# date-shift-r1.net
KiCad netlist of a schematic drawn in EAGLE
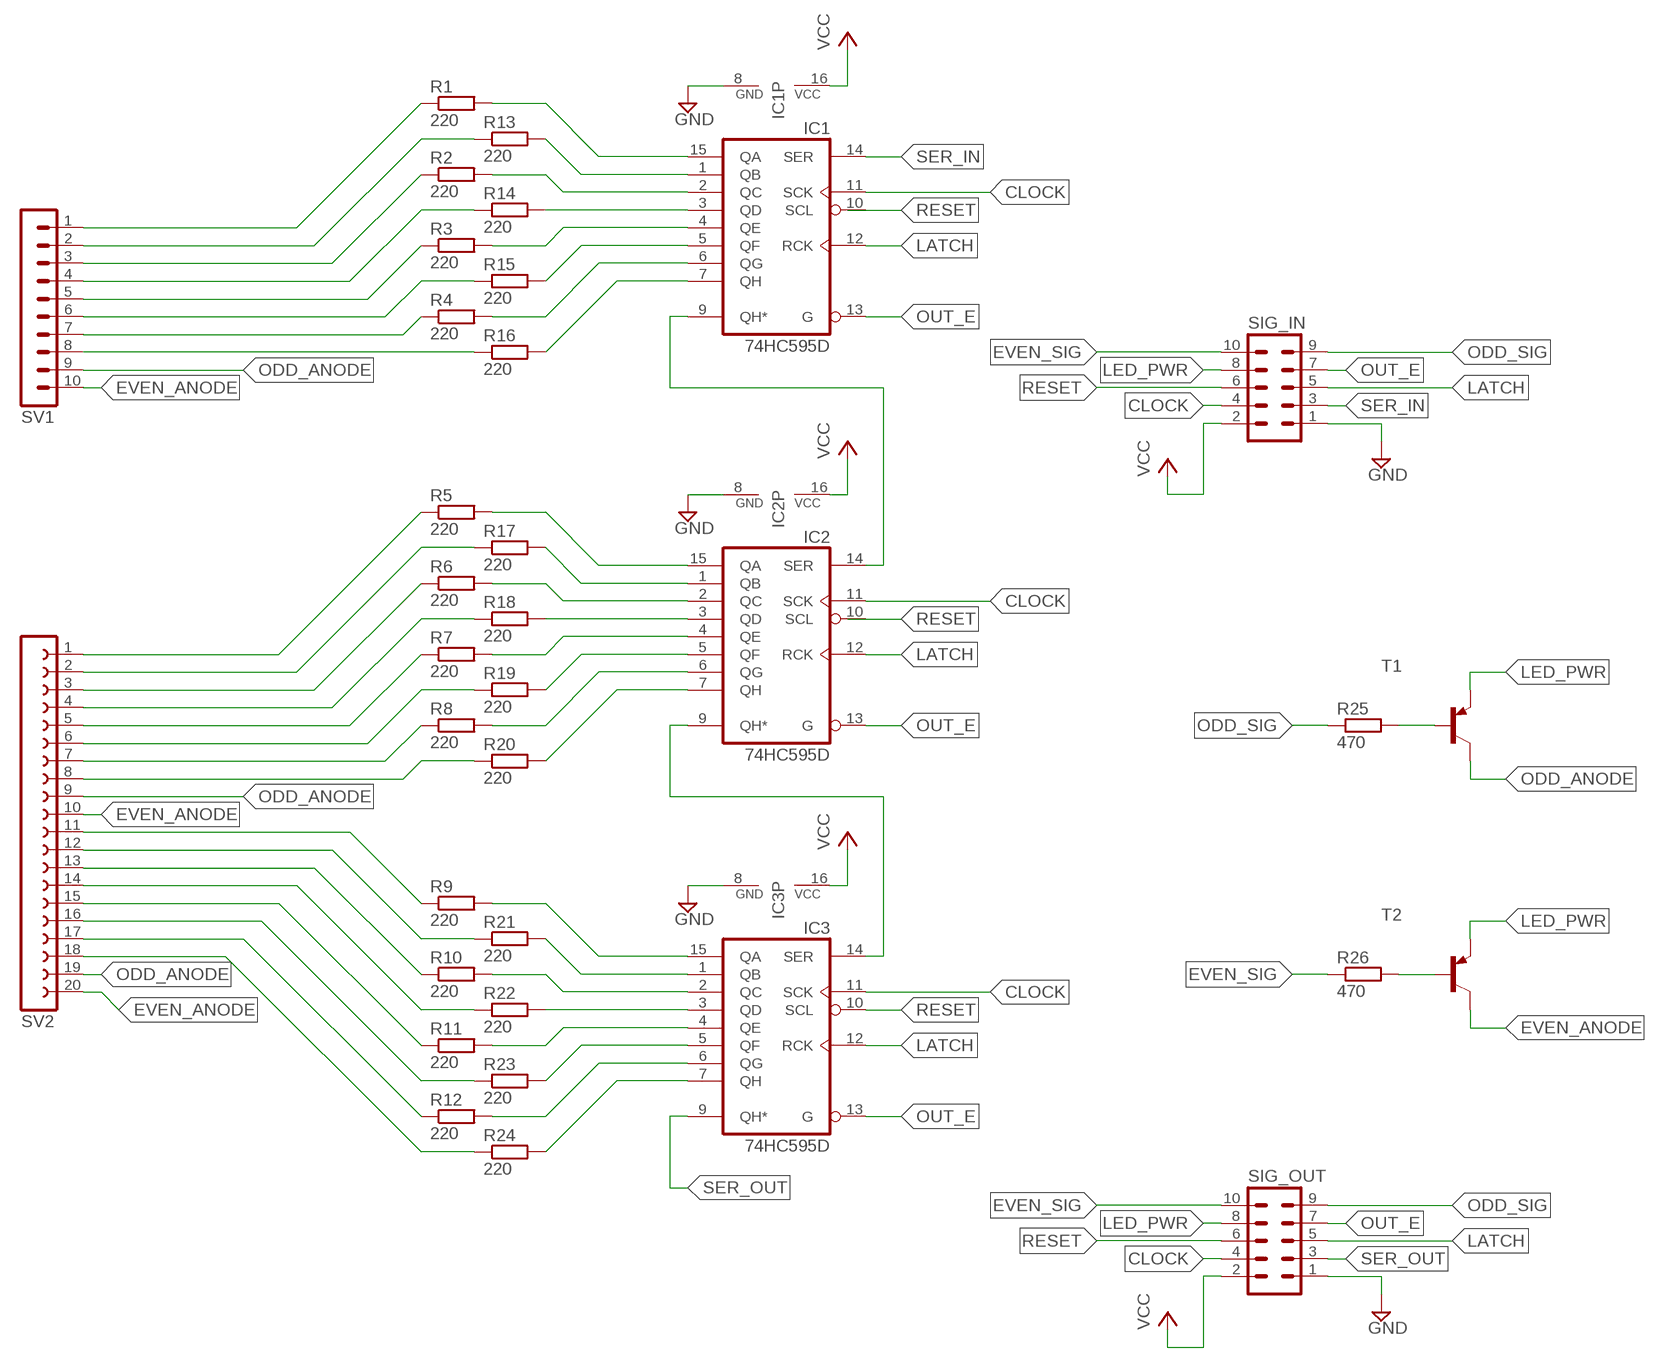
[diagram p0: schematic, sheet 1]

(export (version "E")
  (design (tool "Eeschema 10.0.6"))
  (components
    (comp (ref "IC1")
      (value "74HC595D")
      (footprint "eagle-import:SO16")
      (libsource (lib "eagle-import") (part "74595DHC"))
    )
    (comp (ref "IC2")
      (value "74HC595D")
      (footprint "eagle-import:SO16")
      (libsource (lib "eagle-import") (part "74595DHC"))
    )
    (comp (ref "IC3")
      (value "74HC595D")
      (footprint "eagle-import:SO16")
      (libsource (lib "eagle-import") (part "74595DHC"))
    )
    (comp (ref "R1")
      (value "220")
      (footprint "eagle-import:R0805")
      (libsource (lib "eagle-import") (part "R-EU_R0805"))
    )
    (comp (ref "R2")
      (value "220")
      (footprint "eagle-import:R0805")
      (libsource (lib "eagle-import") (part "R-EU_R0805"))
    )
    (comp (ref "R3")
      (value "220")
      (footprint "eagle-import:R0805")
      (libsource (lib "eagle-import") (part "R-EU_R0805"))
    )
    (comp (ref "R4")
      (value "220")
      (footprint "eagle-import:R0805")
      (libsource (lib "eagle-import") (part "R-EU_R0805"))
    )
    (comp (ref "R5")
      (value "220")
      (footprint "eagle-import:R0805")
      (libsource (lib "eagle-import") (part "R-EU_R0805"))
    )
    (comp (ref "R6")
      (value "220")
      (footprint "eagle-import:R0805")
      (libsource (lib "eagle-import") (part "R-EU_R0805"))
    )
    (comp (ref "R7")
      (value "220")
      (footprint "eagle-import:R0805")
      (libsource (lib "eagle-import") (part "R-EU_R0805"))
    )
    (comp (ref "R8")
      (value "220")
      (footprint "eagle-import:R0805")
      (libsource (lib "eagle-import") (part "R-EU_R0805"))
    )
    (comp (ref "R9")
      (value "220")
      (footprint "eagle-import:R0805")
      (libsource (lib "eagle-import") (part "R-EU_R0805"))
    )
    (comp (ref "R10")
      (value "220")
      (footprint "eagle-import:R0805")
      (libsource (lib "eagle-import") (part "R-EU_R0805"))
    )
    (comp (ref "R11")
      (value "220")
      (footprint "eagle-import:R0805")
      (libsource (lib "eagle-import") (part "R-EU_R0805"))
    )
    (comp (ref "R12")
      (value "220")
      (footprint "eagle-import:R0805")
      (libsource (lib "eagle-import") (part "R-EU_R0805"))
    )
    (comp (ref "R13")
      (value "220")
      (footprint "eagle-import:R0805")
      (libsource (lib "eagle-import") (part "R-EU_R0805"))
    )
    (comp (ref "R14")
      (value "220")
      (footprint "eagle-import:R0805")
      (libsource (lib "eagle-import") (part "R-EU_R0805"))
    )
    (comp (ref "R15")
      (value "220")
      (footprint "eagle-import:R0805")
      (libsource (lib "eagle-import") (part "R-EU_R0805"))
    )
    (comp (ref "R16")
      (value "220")
      (footprint "eagle-import:R0805")
      (libsource (lib "eagle-import") (part "R-EU_R0805"))
    )
    (comp (ref "R17")
      (value "220")
      (footprint "eagle-import:R0805")
      (libsource (lib "eagle-import") (part "R-EU_R0805"))
    )
    (comp (ref "R18")
      (value "220")
      (footprint "eagle-import:R0805")
      (libsource (lib "eagle-import") (part "R-EU_R0805"))
    )
    (comp (ref "R19")
      (value "220")
      (footprint "eagle-import:R0805")
      (libsource (lib "eagle-import") (part "R-EU_R0805"))
    )
    (comp (ref "R20")
      (value "220")
      (footprint "eagle-import:R0805")
      (libsource (lib "eagle-import") (part "R-EU_R0805"))
    )
    (comp (ref "R21")
      (value "220")
      (footprint "eagle-import:R0805")
      (libsource (lib "eagle-import") (part "R-EU_R0805"))
    )
    (comp (ref "R22")
      (value "220")
      (footprint "eagle-import:R0805")
      (libsource (lib "eagle-import") (part "R-EU_R0805"))
    )
    (comp (ref "R23")
      (value "220")
      (footprint "eagle-import:R0805")
      (libsource (lib "eagle-import") (part "R-EU_R0805"))
    )
    (comp (ref "R24")
      (value "220")
      (footprint "eagle-import:R0805")
      (libsource (lib "eagle-import") (part "R-EU_R0805"))
    )
    (comp (ref "R25")
      (value "470")
      (footprint "eagle-import:R0805")
      (libsource (lib "eagle-import") (part "R-EU_R0805"))
    )
    (comp (ref "R26")
      (value "470")
      (footprint "eagle-import:R0805")
      (libsource (lib "eagle-import") (part "R-EU_R0805"))
    )
    (comp (ref "SIG_IN")
      (value "MA05-2")
      (footprint "eagle-import:MA05-2")
      (libsource (lib "eagle-import") (part "MA05-2"))
    )
    (comp (ref "SIG_OUT")
      (value "MA05-2")
      (footprint "eagle-import:MA05-2")
      (libsource (lib "eagle-import") (part "MA05-2"))
    )
    (comp (ref "SV1")
      (value "MA10-1")
      (footprint "eagle-import:MA10-1")
      (libsource (lib "eagle-import") (part "MA10-1"))
    )
    (comp (ref "SV2")
      (value "FE20-1")
      (footprint "eagle-import:FE20")
      (libsource (lib "eagle-import") (part "FE20-1"))
    )
    (comp (ref "T1")
      (value "BC557B-PNP-TO92-EBC")
      (footprint "eagle-import:TO92-EBC")
      (libsource (lib "eagle-import") (part "-PNP-TO92-EBCBC557B"))
    )
    (comp (ref "T2")
      (value "BC557B-PNP-TO92-EBC")
      (footprint "eagle-import:TO92-EBC")
      (libsource (lib "eagle-import") (part "-PNP-TO92-EBCBC557B"))
    )
  )
  (nets
    (net (code "1") (name "CLOCK") (class "Default")
      (node (ref "IC1") (pin "11") (pinfunction "SCK_11") (pintype "input"))
      (node (ref "IC2") (pin "11") (pinfunction "SCK_11") (pintype "input"))
      (node (ref "IC3") (pin "11") (pinfunction "SCK_11") (pintype "input"))
      (node (ref "SIG_IN") (pin "4") (pinfunction "4_4") (pintype "passive"))
      (node (ref "SIG_OUT") (pin "4") (pinfunction "4_4") (pintype "passive"))
    )
    (net (code "2") (name "EVEN_ANODE") (class "Default")
      (node (ref "SV1") (pin "10") (pinfunction "10_10") (pintype "passive"))
      (node (ref "SV2") (pin "10") (pinfunction "10_10") (pintype "passive"))
      (node (ref "SV2") (pin "20") (pinfunction "20_20") (pintype "passive"))
      (node (ref "T2") (pin "C") (pinfunction "C_C") (pintype "passive"))
    )
    (net (code "3") (name "EVEN_SIG") (class "Default")
      (node (ref "R26") (pin "1") (pinfunction "1_1") (pintype "passive"))
      (node (ref "SIG_IN") (pin "10") (pinfunction "10_10") (pintype "passive"))
      (node (ref "SIG_OUT") (pin "10") (pinfunction "10_10") (pintype "passive"))
    )
    (net (code "4") (name "GND") (class "Default")
      (node (ref "IC1") (pin "8") (pinfunction "GND_8") (pintype "power_in"))
      (node (ref "IC2") (pin "8") (pinfunction "GND_8") (pintype "power_in"))
      (node (ref "IC3") (pin "8") (pinfunction "GND_8") (pintype "power_in"))
      (node (ref "SIG_IN") (pin "1") (pinfunction "1_1") (pintype "passive"))
      (node (ref "SIG_OUT") (pin "1") (pinfunction "1_1") (pintype "passive"))
    )
    (net (code "5") (name "LATCH") (class "Default")
      (node (ref "IC1") (pin "12") (pinfunction "RCK_12") (pintype "input"))
      (node (ref "IC2") (pin "12") (pinfunction "RCK_12") (pintype "input"))
      (node (ref "IC3") (pin "12") (pinfunction "RCK_12") (pintype "input"))
      (node (ref "SIG_IN") (pin "5") (pinfunction "5_5") (pintype "passive"))
      (node (ref "SIG_OUT") (pin "5") (pinfunction "5_5") (pintype "passive"))
    )
    (net (code "6") (name "LED_PWR") (class "Default")
      (node (ref "SIG_IN") (pin "8") (pinfunction "8_8") (pintype "passive"))
      (node (ref "SIG_OUT") (pin "8") (pinfunction "8_8") (pintype "passive"))
      (node (ref "T1") (pin "E") (pinfunction "E_E") (pintype "passive"))
      (node (ref "T2") (pin "E") (pinfunction "E_E") (pintype "passive"))
    )
    (net (code "7") (name "Net-(IC1A-QA)") (class "Default")
      (node (ref "IC1") (pin "15") (pinfunction "QA_15") (pintype "tri_state"))
      (node (ref "R1") (pin "2") (pinfunction "2_2") (pintype "passive"))
    )
    (net (code "8") (name "Net-(IC1A-QB)") (class "Default")
      (node (ref "IC1") (pin "1") (pinfunction "QB_1") (pintype "tri_state"))
      (node (ref "R13") (pin "2") (pinfunction "2_2") (pintype "passive"))
    )
    (net (code "9") (name "Net-(IC1A-QC)") (class "Default")
      (node (ref "IC1") (pin "2") (pinfunction "QC_2") (pintype "tri_state"))
      (node (ref "R2") (pin "2") (pinfunction "2_2") (pintype "passive"))
    )
    (net (code "10") (name "Net-(IC1A-QD)") (class "Default")
      (node (ref "IC1") (pin "3") (pinfunction "QD_3") (pintype "tri_state"))
      (node (ref "R14") (pin "2") (pinfunction "2_2") (pintype "passive"))
    )
    (net (code "11") (name "Net-(IC1A-QE)") (class "Default")
      (node (ref "IC1") (pin "4") (pinfunction "QE_4") (pintype "tri_state"))
      (node (ref "R3") (pin "2") (pinfunction "2_2") (pintype "passive"))
    )
    (net (code "12") (name "Net-(IC1A-QF)") (class "Default")
      (node (ref "IC1") (pin "5") (pinfunction "QF_5") (pintype "tri_state"))
      (node (ref "R15") (pin "2") (pinfunction "2_2") (pintype "passive"))
    )
    (net (code "13") (name "Net-(IC1A-QG)") (class "Default")
      (node (ref "IC1") (pin "6") (pinfunction "QG_6") (pintype "tri_state"))
      (node (ref "R4") (pin "2") (pinfunction "2_2") (pintype "passive"))
    )
    (net (code "14") (name "Net-(IC1A-QH)") (class "Default")
      (node (ref "IC1") (pin "7") (pinfunction "QH_7") (pintype "tri_state"))
      (node (ref "R16") (pin "2") (pinfunction "2_2") (pintype "passive"))
    )
    (net (code "15") (name "Net-(IC1A-QH*)") (class "Default")
      (node (ref "IC1") (pin "9") (pinfunction "QH*_9") (pintype "tri_state"))
      (node (ref "IC2") (pin "14") (pinfunction "SER_14") (pintype "input"))
    )
    (net (code "16") (name "Net-(IC2A-QA)") (class "Default")
      (node (ref "IC2") (pin "15") (pinfunction "QA_15") (pintype "tri_state"))
      (node (ref "R5") (pin "2") (pinfunction "2_2") (pintype "passive"))
    )
    (net (code "17") (name "Net-(IC2A-QB)") (class "Default")
      (node (ref "IC2") (pin "1") (pinfunction "QB_1") (pintype "tri_state"))
      (node (ref "R17") (pin "2") (pinfunction "2_2") (pintype "passive"))
    )
    (net (code "18") (name "Net-(IC2A-QC)") (class "Default")
      (node (ref "IC2") (pin "2") (pinfunction "QC_2") (pintype "tri_state"))
      (node (ref "R6") (pin "2") (pinfunction "2_2") (pintype "passive"))
    )
    (net (code "19") (name "Net-(IC2A-QD)") (class "Default")
      (node (ref "IC2") (pin "3") (pinfunction "QD_3") (pintype "tri_state"))
      (node (ref "R18") (pin "2") (pinfunction "2_2") (pintype "passive"))
    )
    (net (code "20") (name "Net-(IC2A-QE)") (class "Default")
      (node (ref "IC2") (pin "4") (pinfunction "QE_4") (pintype "tri_state"))
      (node (ref "R7") (pin "2") (pinfunction "2_2") (pintype "passive"))
    )
    (net (code "21") (name "Net-(IC2A-QF)") (class "Default")
      (node (ref "IC2") (pin "5") (pinfunction "QF_5") (pintype "tri_state"))
      (node (ref "R19") (pin "2") (pinfunction "2_2") (pintype "passive"))
    )
    (net (code "22") (name "Net-(IC2A-QG)") (class "Default")
      (node (ref "IC2") (pin "6") (pinfunction "QG_6") (pintype "tri_state"))
      (node (ref "R8") (pin "2") (pinfunction "2_2") (pintype "passive"))
    )
    (net (code "23") (name "Net-(IC2A-QH)") (class "Default")
      (node (ref "IC2") (pin "7") (pinfunction "QH_7") (pintype "tri_state"))
      (node (ref "R20") (pin "2") (pinfunction "2_2") (pintype "passive"))
    )
    (net (code "24") (name "Net-(IC2A-QH*)") (class "Default")
      (node (ref "IC2") (pin "9") (pinfunction "QH*_9") (pintype "tri_state"))
      (node (ref "IC3") (pin "14") (pinfunction "SER_14") (pintype "input"))
    )
    (net (code "25") (name "Net-(IC3A-QA)") (class "Default")
      (node (ref "IC3") (pin "15") (pinfunction "QA_15") (pintype "tri_state"))
      (node (ref "R9") (pin "2") (pinfunction "2_2") (pintype "passive"))
    )
    (net (code "26") (name "Net-(IC3A-QB)") (class "Default")
      (node (ref "IC3") (pin "1") (pinfunction "QB_1") (pintype "tri_state"))
      (node (ref "R21") (pin "2") (pinfunction "2_2") (pintype "passive"))
    )
    (net (code "27") (name "Net-(IC3A-QC)") (class "Default")
      (node (ref "IC3") (pin "2") (pinfunction "QC_2") (pintype "tri_state"))
      (node (ref "R10") (pin "2") (pinfunction "2_2") (pintype "passive"))
    )
    (net (code "28") (name "Net-(IC3A-QD)") (class "Default")
      (node (ref "IC3") (pin "3") (pinfunction "QD_3") (pintype "tri_state"))
      (node (ref "R22") (pin "2") (pinfunction "2_2") (pintype "passive"))
    )
    (net (code "29") (name "Net-(IC3A-QE)") (class "Default")
      (node (ref "IC3") (pin "4") (pinfunction "QE_4") (pintype "tri_state"))
      (node (ref "R11") (pin "2") (pinfunction "2_2") (pintype "passive"))
    )
    (net (code "30") (name "Net-(IC3A-QF)") (class "Default")
      (node (ref "IC3") (pin "5") (pinfunction "QF_5") (pintype "tri_state"))
      (node (ref "R23") (pin "2") (pinfunction "2_2") (pintype "passive"))
    )
    (net (code "31") (name "Net-(IC3A-QG)") (class "Default")
      (node (ref "IC3") (pin "6") (pinfunction "QG_6") (pintype "tri_state"))
      (node (ref "R12") (pin "2") (pinfunction "2_2") (pintype "passive"))
    )
    (net (code "32") (name "Net-(IC3A-QH)") (class "Default")
      (node (ref "IC3") (pin "7") (pinfunction "QH_7") (pintype "tri_state"))
      (node (ref "R24") (pin "2") (pinfunction "2_2") (pintype "passive"))
    )
    (net (code "33") (name "Net-(R1-Pad1)") (class "Default")
      (node (ref "R1") (pin "1") (pinfunction "1_1") (pintype "passive"))
      (node (ref "SV1") (pin "1") (pinfunction "1_1") (pintype "passive"))
    )
    (net (code "34") (name "Net-(R2-Pad1)") (class "Default")
      (node (ref "R2") (pin "1") (pinfunction "1_1") (pintype "passive"))
      (node (ref "SV1") (pin "3") (pinfunction "3_3") (pintype "passive"))
    )
    (net (code "35") (name "Net-(R3-Pad1)") (class "Default")
      (node (ref "R3") (pin "1") (pinfunction "1_1") (pintype "passive"))
      (node (ref "SV1") (pin "5") (pinfunction "5_5") (pintype "passive"))
    )
    (net (code "36") (name "Net-(R4-Pad1)") (class "Default")
      (node (ref "R4") (pin "1") (pinfunction "1_1") (pintype "passive"))
      (node (ref "SV1") (pin "7") (pinfunction "7_7") (pintype "passive"))
    )
    (net (code "37") (name "Net-(R5-Pad1)") (class "Default")
      (node (ref "R5") (pin "1") (pinfunction "1_1") (pintype "passive"))
      (node (ref "SV2") (pin "1") (pinfunction "1_1") (pintype "passive"))
    )
    (net (code "38") (name "Net-(R6-Pad1)") (class "Default")
      (node (ref "R6") (pin "1") (pinfunction "1_1") (pintype "passive"))
      (node (ref "SV2") (pin "3") (pinfunction "3_3") (pintype "passive"))
    )
    (net (code "39") (name "Net-(R7-Pad1)") (class "Default")
      (node (ref "R7") (pin "1") (pinfunction "1_1") (pintype "passive"))
      (node (ref "SV2") (pin "5") (pinfunction "5_5") (pintype "passive"))
    )
    (net (code "40") (name "Net-(R8-Pad1)") (class "Default")
      (node (ref "R8") (pin "1") (pinfunction "1_1") (pintype "passive"))
      (node (ref "SV2") (pin "7") (pinfunction "7_7") (pintype "passive"))
    )
    (net (code "41") (name "Net-(R9-Pad1)") (class "Default")
      (node (ref "R9") (pin "1") (pinfunction "1_1") (pintype "passive"))
      (node (ref "SV2") (pin "11") (pinfunction "11_11") (pintype "passive"))
    )
    (net (code "42") (name "Net-(R10-Pad1)") (class "Default")
      (node (ref "R10") (pin "1") (pinfunction "1_1") (pintype "passive"))
      (node (ref "SV2") (pin "13") (pinfunction "13_13") (pintype "passive"))
    )
    (net (code "43") (name "Net-(R11-Pad1)") (class "Default")
      (node (ref "R11") (pin "1") (pinfunction "1_1") (pintype "passive"))
      (node (ref "SV2") (pin "15") (pinfunction "15_15") (pintype "passive"))
    )
    (net (code "44") (name "Net-(R12-Pad1)") (class "Default")
      (node (ref "R12") (pin "1") (pinfunction "1_1") (pintype "passive"))
      (node (ref "SV2") (pin "17") (pinfunction "17_17") (pintype "passive"))
    )
    (net (code "45") (name "Net-(R13-Pad1)") (class "Default")
      (node (ref "R13") (pin "1") (pinfunction "1_1") (pintype "passive"))
      (node (ref "SV1") (pin "2") (pinfunction "2_2") (pintype "passive"))
    )
    (net (code "46") (name "Net-(R14-Pad1)") (class "Default")
      (node (ref "R14") (pin "1") (pinfunction "1_1") (pintype "passive"))
      (node (ref "SV1") (pin "4") (pinfunction "4_4") (pintype "passive"))
    )
    (net (code "47") (name "Net-(R15-Pad1)") (class "Default")
      (node (ref "R15") (pin "1") (pinfunction "1_1") (pintype "passive"))
      (node (ref "SV1") (pin "6") (pinfunction "6_6") (pintype "passive"))
    )
    (net (code "48") (name "Net-(R16-Pad1)") (class "Default")
      (node (ref "R16") (pin "1") (pinfunction "1_1") (pintype "passive"))
      (node (ref "SV1") (pin "8") (pinfunction "8_8") (pintype "passive"))
    )
    (net (code "49") (name "Net-(R17-Pad1)") (class "Default")
      (node (ref "R17") (pin "1") (pinfunction "1_1") (pintype "passive"))
      (node (ref "SV2") (pin "2") (pinfunction "2_2") (pintype "passive"))
    )
    (net (code "50") (name "Net-(R18-Pad1)") (class "Default")
      (node (ref "R18") (pin "1") (pinfunction "1_1") (pintype "passive"))
      (node (ref "SV2") (pin "4") (pinfunction "4_4") (pintype "passive"))
    )
    (net (code "51") (name "Net-(R19-Pad1)") (class "Default")
      (node (ref "R19") (pin "1") (pinfunction "1_1") (pintype "passive"))
      (node (ref "SV2") (pin "6") (pinfunction "6_6") (pintype "passive"))
    )
    (net (code "52") (name "Net-(R20-Pad1)") (class "Default")
      (node (ref "R20") (pin "1") (pinfunction "1_1") (pintype "passive"))
      (node (ref "SV2") (pin "8") (pinfunction "8_8") (pintype "passive"))
    )
    (net (code "53") (name "Net-(R21-Pad1)") (class "Default")
      (node (ref "R21") (pin "1") (pinfunction "1_1") (pintype "passive"))
      (node (ref "SV2") (pin "12") (pinfunction "12_12") (pintype "passive"))
    )
    (net (code "54") (name "Net-(R22-Pad1)") (class "Default")
      (node (ref "R22") (pin "1") (pinfunction "1_1") (pintype "passive"))
      (node (ref "SV2") (pin "14") (pinfunction "14_14") (pintype "passive"))
    )
    (net (code "55") (name "Net-(R23-Pad1)") (class "Default")
      (node (ref "R23") (pin "1") (pinfunction "1_1") (pintype "passive"))
      (node (ref "SV2") (pin "16") (pinfunction "16_16") (pintype "passive"))
    )
    (net (code "56") (name "Net-(R24-Pad1)") (class "Default")
      (node (ref "R24") (pin "1") (pinfunction "1_1") (pintype "passive"))
      (node (ref "SV2") (pin "18") (pinfunction "18_18") (pintype "passive"))
    )
    (net (code "57") (name "Net-(R25-Pad2)") (class "Default")
      (node (ref "R25") (pin "2") (pinfunction "2_2") (pintype "passive"))
      (node (ref "T1") (pin "B") (pinfunction "B_B") (pintype "passive"))
    )
    (net (code "58") (name "Net-(R26-Pad2)") (class "Default")
      (node (ref "R26") (pin "2") (pinfunction "2_2") (pintype "passive"))
      (node (ref "T2") (pin "B") (pinfunction "B_B") (pintype "passive"))
    )
    (net (code "59") (name "ODD_ANODE") (class "Default")
      (node (ref "SV1") (pin "9") (pinfunction "9_9") (pintype "passive"))
      (node (ref "SV2") (pin "19") (pinfunction "19_19") (pintype "passive"))
      (node (ref "SV2") (pin "9") (pinfunction "9_9") (pintype "passive"))
      (node (ref "T1") (pin "C") (pinfunction "C_C") (pintype "passive"))
    )
    (net (code "60") (name "ODD_SIG") (class "Default")
      (node (ref "R25") (pin "1") (pinfunction "1_1") (pintype "passive"))
      (node (ref "SIG_IN") (pin "9") (pinfunction "9_9") (pintype "passive"))
      (node (ref "SIG_OUT") (pin "9") (pinfunction "9_9") (pintype "passive"))
    )
    (net (code "61") (name "OUT_E") (class "Default")
      (node (ref "IC1") (pin "13") (pinfunction "G_13") (pintype "input"))
      (node (ref "IC2") (pin "13") (pinfunction "G_13") (pintype "input"))
      (node (ref "IC3") (pin "13") (pinfunction "G_13") (pintype "input"))
      (node (ref "SIG_IN") (pin "7") (pinfunction "7_7") (pintype "passive"))
      (node (ref "SIG_OUT") (pin "7") (pinfunction "7_7") (pintype "passive"))
    )
    (net (code "62") (name "RESET") (class "Default")
      (node (ref "IC3") (pin "10") (pinfunction "SCL_10") (pintype "input"))
      (node (ref "SIG_IN") (pin "6") (pinfunction "6_6") (pintype "passive"))
      (node (ref "SIG_OUT") (pin "6") (pinfunction "6_6") (pintype "passive"))
    )
    (net (code "63") (name "SER_IN") (class "Default")
      (node (ref "IC1") (pin "14") (pinfunction "SER_14") (pintype "input"))
      (node (ref "SIG_IN") (pin "3") (pinfunction "3_3") (pintype "passive"))
    )
    (net (code "64") (name "SER_OUT") (class "Default")
      (node (ref "IC3") (pin "9") (pinfunction "QH*_9") (pintype "tri_state"))
      (node (ref "SIG_OUT") (pin "3") (pinfunction "3_3") (pintype "passive"))
    )
    (net (code "65") (name "VCC") (class "Default")
      (node (ref "IC1") (pin "16") (pinfunction "VCC_16") (pintype "power_in"))
      (node (ref "IC2") (pin "16") (pinfunction "VCC_16") (pintype "power_in"))
      (node (ref "IC3") (pin "16") (pinfunction "VCC_16") (pintype "power_in"))
      (node (ref "SIG_IN") (pin "2") (pinfunction "2_2") (pintype "passive"))
      (node (ref "SIG_OUT") (pin "2") (pinfunction "2_2") (pintype "passive"))
    )
    (net (code "66") (name "unconnected-(IC1A-SCL-Pad10)") (class "Default")
      (node (ref "IC1") (pin "10") (pinfunction "SCL_10") (pintype "input"))
    )
    (net (code "67") (name "unconnected-(IC2A-SCL-Pad10)") (class "Default")
      (node (ref "IC2") (pin "10") (pinfunction "SCL_10") (pintype "input"))
    )
  )
)
